# Encoders.net
KiCad netlist of a schematic drawn in Altium Designer
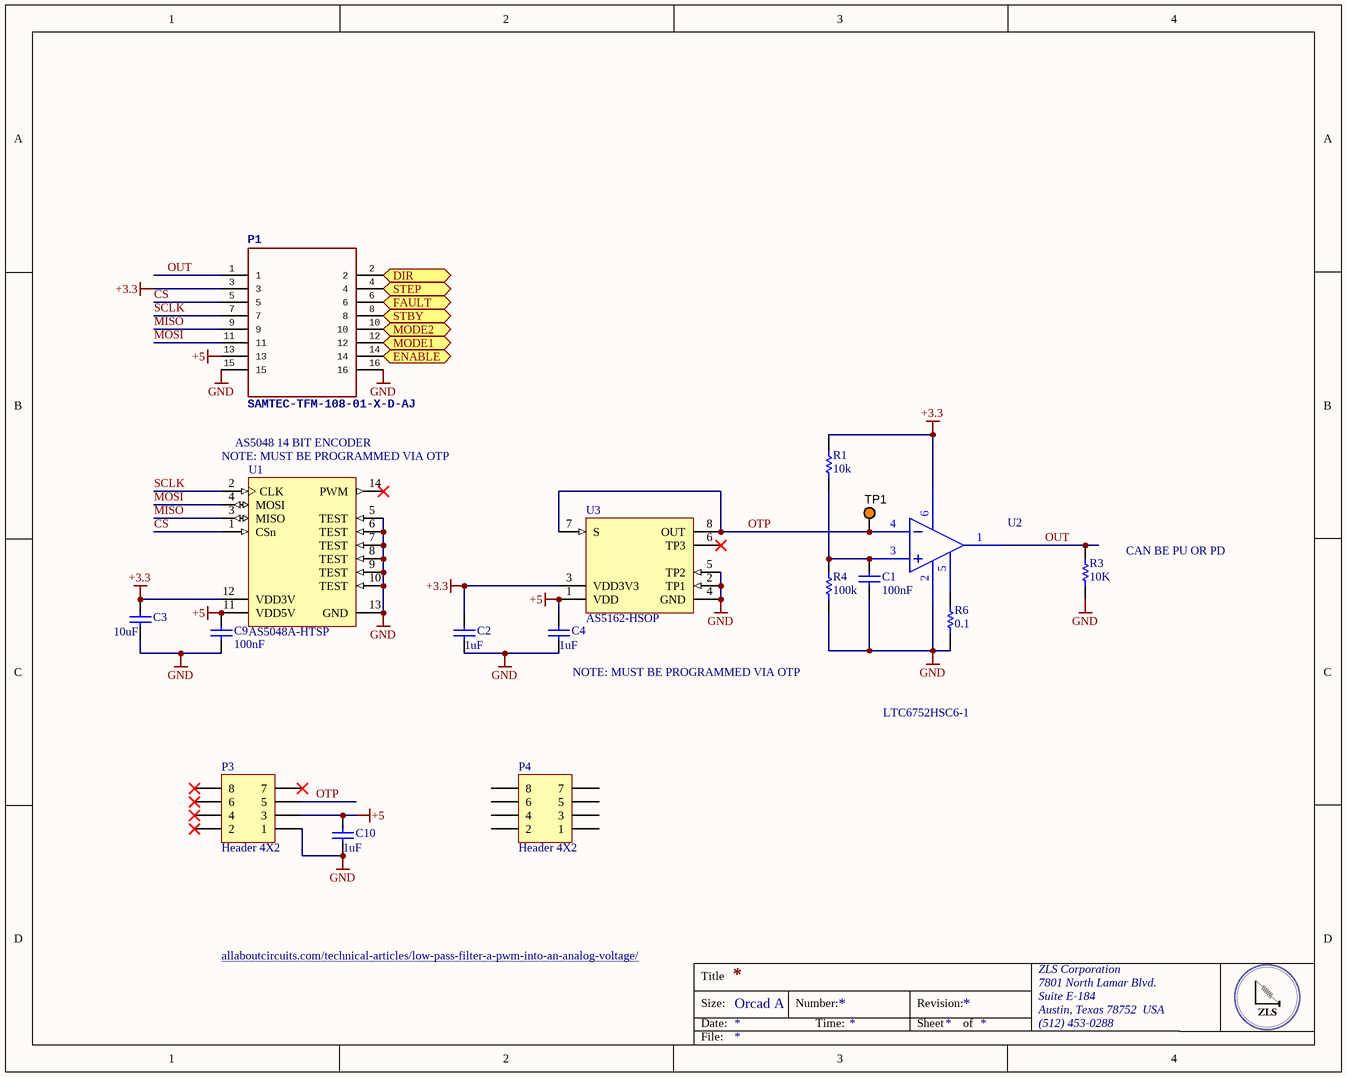
[diagram p0: Encoders.SchDoc]

(export (version "E")
  (design (tool "Eeschema 10.0.6"))
  (components
    (comp (ref "C1")
      (value "VJ0805Y104KXXCW1BC")
      (footprint "CAPC2013X135X50ML15T20")
      (description "0.1µF ±10% 25V Ceramic Capacitor X7R 0805 (2012 Metric)")
      (fields
        (field (name "MANUFACTURER") "Vitramon")
        (field (name "CAPACITANCE") "100nF")
        (field (name "TOLERANCE") "10%")
      )
      (libsource (lib "Altium Content Vault") (part "CAP"))
    )
    (comp (ref "C2")
      (value "1uF")
      (footprint "CAPC2013X135X50ML15T20")
      (description "0.1µF ±10% 25V Ceramic Capacitor X7R 0805 (2012 Metric)")
      (libsource (lib "Altium Content Vault") (part "CMP-2007-03442-1"))
    )
    (comp (ref "C3")
      (value "10uF")
      (footprint "CAPC2013X135X50ML15T20")
      (description "0.1µF ±10% 25V Ceramic Capacitor X7R 0805 (2012 Metric)")
      (libsource (lib "Altium Content Vault") (part "CMP-2007-03442-1"))
    )
    (comp (ref "C4")
      (value "1uF")
      (footprint "CAPC2013X135X50ML15T20")
      (description "0.1µF ±10% 25V Ceramic Capacitor X7R 0805 (2012 Metric)")
      (libsource (lib "Altium Content Vault") (part "CMP-2007-03442-1"))
    )
    (comp (ref "C9")
      (value "VJ0805Y104KXXCW1BC")
      (footprint "CAPC2013X135X50ML15T20")
      (description "0.1µF ±10% 25V Ceramic Capacitor X7R 0805 (2012 Metric)")
      (fields
        (field (name "MANUFACTURER") "Vitramon")
        (field (name "CAPACITANCE") "100nF")
        (field (name "TOLERANCE") "10%")
      )
      (libsource (lib "Altium Content Vault") (part "CAP"))
    )
    (comp (ref "C10")
      (value "1uF")
      (footprint "CAPC2013X135X50ML15T20")
      (description "0.1µF ±10% 25V Ceramic Capacitor X7R 0805 (2012 Metric)")
      (libsource (lib "Altium Content Vault") (part "CMP-2007-03442-1"))
    )
    (comp (ref "P1")
      (value "SAMTEC-TFM-108-01-X-D-AJ")
      (footprint "SAMTEC-TFM-108-01-X-D-A")
      (libsource (lib "SAMTEC-TFM-108-01-X-D-A") (part "SAMTEC-TFM-108-01-X-D-AJ"))
    )
    (comp (ref "P3")
      (value "Header 4X2")
      (footprint "HDR2X4")
      (description "Header, 4-Pin, Dual row")
      (fields (field (name "PUBLISHER") "Altium Limited"))
      (libsource (lib "Miscellaneous Connectors") (part "Header 4X2"))
    )
    (comp (ref "P4")
      (value "Header 4X2")
      (footprint "HDR2X4")
      (description "Header, 4-Pin, Dual row")
      (fields (field (name "PUBLISHER") "Altium Limited"))
      (libsource (lib "Miscellaneous Connectors") (part "Header 4X2"))
    )
    (comp (ref "R1")
      (value "10k")
      (footprint "RESC0603(1608)_N")
      (description "0R12 0.1W 1% 0603 (1608 Metric)  SMD")
      (libsource (lib "Altium Content Vault") (part "CMP-1012-00511-1"))
    )
    (comp (ref "R3")
      (value "10K")
      (footprint "RESC0603(1608)_N")
      (description "0R12 0.1W 1% 0603 (1608 Metric)  SMD")
      (fields (field (name "POWER") "0.1 W") (field (name "TOLERANCE") "1 %"))
      (libsource (lib "Altium Content Vault") (part "CMP-1012-00511-1"))
    )
    (comp (ref "R4")
      (value "100k")
      (footprint "RESC0603(1608)_N")
      (description "0R12 0.1W 1% 0603 (1608 Metric)  SMD")
      (libsource (lib "Altium Content Vault") (part "CMP-1012-00511-1"))
    )
    (comp (ref "R6")
      (value "0.1")
      (footprint "RESC0603(1608)_N")
      (description "0R12 0.1W 1% 0603 (1608 Metric)  SMD")
      (fields (field (name "POWER") "0.1 W") (field (name "TOLERANCE") "1 %"))
      (libsource (lib "Altium Content Vault") (part "RES"))
    )
    (comp (ref "TP1")
      (value "5003")
      (footprint "KSTN-5003")
      (description "Test Point, Orange, 1-Pin THD, RoHS")
      (libsource (lib "Altium Content Vault") (part "CMP-1672-00009-1"))
    )
    (comp (ref "U1")
      (value "AS5048A-HTSP")
      (footprint "AMS-TSSOP-14-5000X4400DE_N")
      (description "Magnetic Rotary Encoder 14-bit Angular Position Sensor, 3.3 or 5 V, TSSOP-14, Pb-Free, Reel")
      (fields (field (name "MANUFACTURER") "AMS"))
      (libsource (lib "Altium Content Vault") (part "CMP-0555-00034-2"))
    )
    (comp (ref "U2")
      (value "LTC6752HSC6-1TRMPBF")
      (description "IC COMP R-R CMOS 280MHZ SC70-6")
      (libsource (lib "ZLS_Schematic_lib") (part "LTC6752HSC6-1TRMPBF"))
    )
    (comp (ref "U3")
      (value "AS5162-HSOP")
      (footprint "AMS-SOIC-8-4900X3900DE_N")
      (description "12-Bit Magnetic Angle Position Sensor, 4.5 to 5.5 V, SOIC-8, Pb-Free, Reel")
      (fields (field (name "MANUFACTURER") "AMS"))
      (libsource (lib "Altium Content Vault") (part "CMP-0555-00008-2"))
    )
  )
  (nets
    (net (code "1") (name "+3.3") (class "Default")
      (node (ref "C2") (pin "2") (pinfunction "2_2") (pintype "passive"))
      (node (ref "C3") (pin "2") (pinfunction "2_2") (pintype "passive"))
      (node (ref "P1") (pin "3") (pinfunction "3_3") (pintype "passive"))
      (node (ref "R1") (pin "2") (pinfunction "2_2") (pintype "passive"))
      (node (ref "U1") (pin "12") (pinfunction "VDD3V_12") (pintype "power_in"))
      (node (ref "U2") (pin "6") (pinfunction "V+_6") (pintype "passive"))
      (node (ref "U3") (pin "3") (pinfunction "VDD3V3_3") (pintype "power_in"))
    )
    (net (code "2") (name "+5") (class "Default")
      (node (ref "C10") (pin "2") (pinfunction "2_2") (pintype "passive"))
      (node (ref "C4") (pin "2") (pinfunction "2_2") (pintype "passive"))
      (node (ref "C9") (pin "2") (pinfunction "2_2") (pintype "passive"))
      (node (ref "P1") (pin "13") (pinfunction "13_13") (pintype "passive"))
      (node (ref "P3") (pin "3") (pinfunction "3_3") (pintype "passive"))
      (node (ref "U1") (pin "11") (pinfunction "VDD5V_11") (pintype "power_in"))
      (node (ref "U3") (pin "1") (pinfunction "VDD_1") (pintype "power_in"))
    )
    (net (code "3") (name "/CS") (class "Default")
      (node (ref "P1") (pin "5") (pinfunction "5_5") (pintype "passive"))
      (node (ref "U1") (pin "1") (pinfunction "CSn_1") (pintype "input"))
    )
    (net (code "4") (name "/DIR") (class "Default")
      (node (ref "P1") (pin "2") (pinfunction "2_2") (pintype "passive"))
    )
    (net (code "5") (name "/ENABLE") (class "Default")
      (node (ref "P1") (pin "14") (pinfunction "14_14") (pintype "passive"))
    )
    (net (code "6") (name "/FAULT") (class "Default")
      (node (ref "P1") (pin "6") (pinfunction "6_6") (pintype "passive"))
    )
    (net (code "7") (name "/MISO") (class "Default")
      (node (ref "P1") (pin "9") (pinfunction "9_9") (pintype "passive"))
      (node (ref "U1") (pin "3") (pinfunction "MISO_3") (pintype "bidirectional"))
    )
    (net (code "8") (name "/MODE1") (class "Default")
      (node (ref "P1") (pin "12") (pinfunction "12_12") (pintype "passive"))
    )
    (net (code "9") (name "/MODE2") (class "Default")
      (node (ref "P1") (pin "10") (pinfunction "10_10") (pintype "passive"))
    )
    (net (code "10") (name "/MOSI") (class "Default")
      (node (ref "P1") (pin "11") (pinfunction "11_11") (pintype "passive"))
      (node (ref "U1") (pin "4") (pinfunction "MOSI_4") (pintype "bidirectional"))
    )
    (net (code "11") (name "/OTP") (class "Default")
      (node (ref "P3") (pin "5") (pinfunction "5_5") (pintype "passive"))
      (node (ref "TP1") (pin "1") (pinfunction "1_1") (pintype "passive"))
      (node (ref "U2") (pin "4") (pinfunction "-IN_4") (pintype "passive"))
      (node (ref "U3") (pin "7") (pinfunction "S_7") (pintype "input"))
      (node (ref "U3") (pin "8") (pinfunction "OUT_8") (pintype "tri_state"))
    )
    (net (code "12") (name "/OUT") (class "Default")
      (node (ref "P1") (pin "1") (pinfunction "1_1") (pintype "passive"))
      (node (ref "R3") (pin "2") (pinfunction "2_2") (pintype "passive"))
      (node (ref "U2") (pin "1") (pinfunction "OUT_1") (pintype "passive"))
    )
    (net (code "13") (name "/SCLK") (class "Default")
      (node (ref "P1") (pin "7") (pinfunction "7_7") (pintype "passive"))
      (node (ref "U1") (pin "2") (pinfunction "CLK_2") (pintype "input"))
    )
    (net (code "14") (name "/STBY") (class "Default")
      (node (ref "P1") (pin "8") (pinfunction "8_8") (pintype "passive"))
    )
    (net (code "15") (name "/STEP") (class "Default")
      (node (ref "P1") (pin "4") (pinfunction "4_4") (pintype "passive"))
    )
    (net (code "16") (name "GND") (class "Default")
      (node (ref "C1") (pin "1") (pinfunction "1_1") (pintype "passive"))
      (node (ref "C10") (pin "1") (pinfunction "1_1") (pintype "passive"))
      (node (ref "C2") (pin "1") (pinfunction "1_1") (pintype "passive"))
      (node (ref "C3") (pin "1") (pinfunction "1_1") (pintype "passive"))
      (node (ref "C4") (pin "1") (pinfunction "1_1") (pintype "passive"))
      (node (ref "C9") (pin "1") (pinfunction "1_1") (pintype "passive"))
      (node (ref "P1") (pin "15") (pinfunction "15_15") (pintype "passive"))
      (node (ref "P1") (pin "16") (pinfunction "16_16") (pintype "passive"))
      (node (ref "P3") (pin "1") (pinfunction "1_1") (pintype "passive"))
      (node (ref "R3") (pin "1") (pinfunction "1_1") (pintype "passive"))
      (node (ref "R4") (pin "1") (pinfunction "1_1") (pintype "passive"))
      (node (ref "R6") (pin "1") (pinfunction "1_1") (pintype "passive"))
      (node (ref "U1") (pin "10") (pinfunction "TEST_10") (pintype "input"))
      (node (ref "U1") (pin "13") (pinfunction "GND_13") (pintype "power_in"))
      (node (ref "U1") (pin "5") (pinfunction "TEST_5") (pintype "input"))
      (node (ref "U1") (pin "6") (pinfunction "TEST_6") (pintype "input"))
      (node (ref "U1") (pin "7") (pinfunction "TEST_7") (pintype "input"))
      (node (ref "U1") (pin "8") (pinfunction "TEST_8") (pintype "input"))
      (node (ref "U1") (pin "9") (pinfunction "TEST_9") (pintype "input"))
      (node (ref "U2") (pin "2") (pinfunction "V-_2") (pintype "passive"))
      (node (ref "U3") (pin "2") (pinfunction "TP1_2") (pintype "input"))
      (node (ref "U3") (pin "4") (pinfunction "GND_4") (pintype "power_in"))
      (node (ref "U3") (pin "5") (pinfunction "TP2_5") (pintype "input"))
    )
    (net (code "17") (name "Net-(U2-+IN)") (class "Default")
      (node (ref "C1") (pin "2") (pinfunction "2_2") (pintype "passive"))
      (node (ref "R1") (pin "1") (pinfunction "1_1") (pintype "passive"))
      (node (ref "R4") (pin "2") (pinfunction "2_2") (pintype "passive"))
      (node (ref "U2") (pin "3") (pinfunction "+IN_3") (pintype "passive"))
    )
    (net (code "18") (name "Net-(U2-HYS)") (class "Default")
      (node (ref "R6") (pin "2") (pinfunction "2_2") (pintype "passive"))
      (node (ref "U2") (pin "5") (pinfunction "HYS_5") (pintype "passive"))
    )
    (net (code "19") (name "unconnected-(P3-Pad2)") (class "Default")
      (node (ref "P3") (pin "2") (pinfunction "2_2") (pintype "passive+no_connect"))
    )
    (net (code "20") (name "unconnected-(P3-Pad4)") (class "Default")
      (node (ref "P3") (pin "4") (pinfunction "4_4") (pintype "passive+no_connect"))
    )
    (net (code "21") (name "unconnected-(P3-Pad6)") (class "Default")
      (node (ref "P3") (pin "6") (pinfunction "6_6") (pintype "passive+no_connect"))
    )
    (net (code "22") (name "unconnected-(P3-Pad7)") (class "Default")
      (node (ref "P3") (pin "7") (pinfunction "7_7") (pintype "passive+no_connect"))
    )
    (net (code "23") (name "unconnected-(P3-Pad8)") (class "Default")
      (node (ref "P3") (pin "8") (pinfunction "8_8") (pintype "passive+no_connect"))
    )
    (net (code "24") (name "unconnected-(P4-Pad1)") (class "Default")
      (node (ref "P4") (pin "1") (pinfunction "1_1") (pintype "passive"))
    )
    (net (code "25") (name "unconnected-(P4-Pad2)") (class "Default")
      (node (ref "P4") (pin "2") (pinfunction "2_2") (pintype "passive"))
    )
    (net (code "26") (name "unconnected-(P4-Pad3)") (class "Default")
      (node (ref "P4") (pin "3") (pinfunction "3_3") (pintype "passive"))
    )
    (net (code "27") (name "unconnected-(P4-Pad4)") (class "Default")
      (node (ref "P4") (pin "4") (pinfunction "4_4") (pintype "passive"))
    )
    (net (code "28") (name "unconnected-(P4-Pad5)") (class "Default")
      (node (ref "P4") (pin "5") (pinfunction "5_5") (pintype "passive"))
    )
    (net (code "29") (name "unconnected-(P4-Pad6)") (class "Default")
      (node (ref "P4") (pin "6") (pinfunction "6_6") (pintype "passive"))
    )
    (net (code "30") (name "unconnected-(P4-Pad7)") (class "Default")
      (node (ref "P4") (pin "7") (pinfunction "7_7") (pintype "passive"))
    )
    (net (code "31") (name "unconnected-(P4-Pad8)") (class "Default")
      (node (ref "P4") (pin "8") (pinfunction "8_8") (pintype "passive"))
    )
    (net (code "32") (name "unconnected-(U1-PWM-Pad14)") (class "Default")
      (node (ref "U1") (pin "14") (pinfunction "PWM_14") (pintype "output+no_connect"))
    )
    (net (code "33") (name "unconnected-(U3-TP3-Pad6)") (class "Default")
      (node (ref "U3") (pin "6") (pinfunction "TP3_6") (pintype "passive+no_connect"))
    )
  )
)
